# MAX30105_Breakout.net
KiCad netlist of a schematic drawn in EAGLE
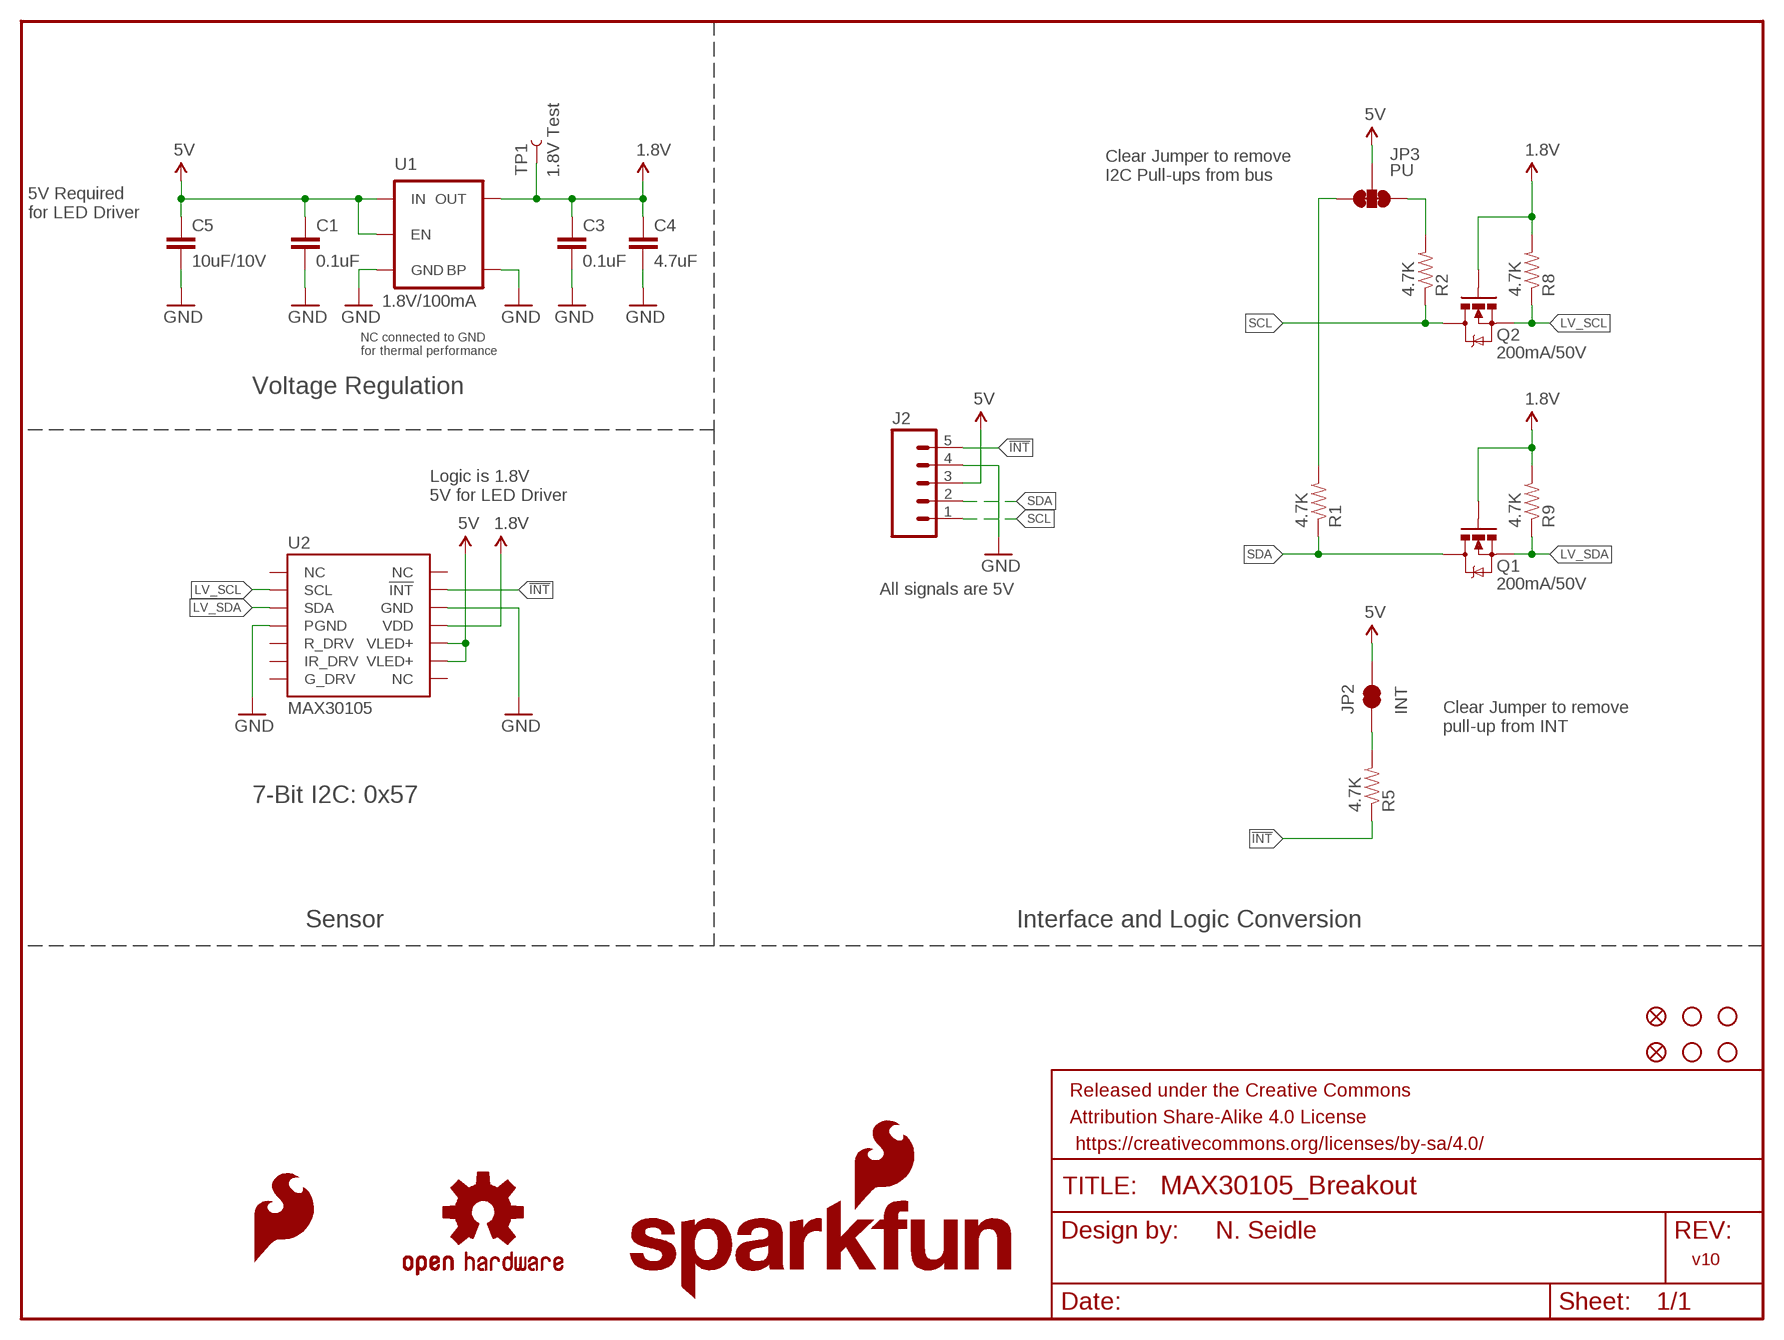
[diagram p0: schematic, sheet 1]

(export (version "E")
  (design (tool "Eeschema 10.0.6"))
  (components
    (comp (ref "C1")
      (value "0.1uF")
      (footprint "eagle-import:0603-CAP")
      (libsource (lib "eagle-import") (part "0.1UF-25V(+80/-20%)(0603)"))
    )
    (comp (ref "C3")
      (value "0.1uF")
      (footprint "eagle-import:0603-CAP")
      (libsource (lib "eagle-import") (part "0.1UF-25V(+80/-20%)(0603)"))
    )
    (comp (ref "C4")
      (value "4.7uF")
      (footprint "eagle-import:0603-CAP")
      (libsource (lib "eagle-import") (part "4.7UF-6.3V-10%(0603)0603"))
    )
    (comp (ref "C5")
      (value "10uF/10V")
      (footprint "eagle-import:0805-CAP")
      (libsource (lib "eagle-import") (part "10UF10V10%(0805)"))
    )
    (comp (ref "FID1")
      (value "FIDUCIAL1X2")
      (footprint "eagle-import:FIDUCIAL-1X2")
      (libsource (lib "eagle-import") (part "FIDUCIAL1X2"))
    )
    (comp (ref "FID2")
      (value "FIDUCIAL1X2")
      (footprint "eagle-import:FIDUCIAL-1X2")
      (libsource (lib "eagle-import") (part "FIDUCIAL1X2"))
    )
    (comp (ref "FRAME1")
      (value "FRAME-LETTER")
      (footprint "eagle-import:CREATIVE_COMMONS")
      (libsource (lib "eagle-import") (part "FRAME-LETTER"))
    )
    (comp (ref "J2")
      (value "M05PTH")
      (footprint "eagle-import:1X05")
      (libsource (lib "eagle-import") (part "M05PTH"))
    )
    (comp (ref "JP2")
      (value "INT")
      (footprint "eagle-import:PAD-JUMPER-2-NC_BY_TRACE_YES_SILK")
      (libsource (lib "eagle-import") (part "JUMPER-PAD-2-NC_BY_TRACE"))
    )
    (comp (ref "JP3")
      (value "PU")
      (footprint "eagle-import:PAD-JUMPER-3-3OF3_NC_BY_TRACE_YES_SILK_FULL_BOX")
      (libsource (lib "eagle-import") (part "JUMPER-PAD-3-NC_BY_TRACE"))
    )
    (comp (ref "LOGO1")
      (value "SFE_LOGO_NAME_FLAME.1_INCH")
      (footprint "eagle-import:SFE_LOGO_NAME_FLAME_.1")
      (libsource (lib "eagle-import") (part "SFE_LOGO_NAME_FLAME.1_INCH"))
    )
    (comp (ref "LOGO2")
      (value "OSHW-LOGOS")
      (footprint "eagle-import:OSHW-LOGO-S")
      (libsource (lib "eagle-import") (part "OSHW-LOGOS"))
    )
    (comp (ref "LOGO4")
      (value "SFE_LOGO_FLAME.1EXP")
      (footprint "eagle-import:SFE_LOGO_FLAME_COPPER_EXPOSED_.1")
      (libsource (lib "eagle-import") (part "SFE_LOGO_FLAME.1EXP"))
    )
    (comp (ref "Q1")
      (value "200mA/50V")
      (footprint "eagle-import:SOT23-3")
      (libsource (lib "eagle-import") (part "MOSFET-NCHANNELBSS138"))
    )
    (comp (ref "Q2")
      (value "200mA/50V")
      (footprint "eagle-import:SOT23-3")
      (libsource (lib "eagle-import") (part "MOSFET-NCHANNELBSS138"))
    )
    (comp (ref "R1")
      (value "4.7K")
      (footprint "eagle-import:0603-RES")
      (libsource (lib "eagle-import") (part "4.7KOHM-1/10W-1%(0603)"))
    )
    (comp (ref "R2")
      (value "4.7K")
      (footprint "eagle-import:0603-RES")
      (libsource (lib "eagle-import") (part "4.7KOHM-1/10W-1%(0603)"))
    )
    (comp (ref "R5")
      (value "4.7K")
      (footprint "eagle-import:0603-RES")
      (libsource (lib "eagle-import") (part "4.7KOHM-1/10W-1%(0603)"))
    )
    (comp (ref "R8")
      (value "4.7K")
      (footprint "eagle-import:0603-RES")
      (libsource (lib "eagle-import") (part "4.7KOHM-1/10W-1%(0603)"))
    )
    (comp (ref "R9")
      (value "4.7K")
      (footprint "eagle-import:0603-RES")
      (libsource (lib "eagle-import") (part "4.7KOHM-1/10W-1%(0603)"))
    )
    (comp (ref "STANDOFF1")
      (value "STAND-OFF")
      (footprint "eagle-import:STAND-OFF")
      (libsource (lib "eagle-import") (part "STAND-OFF"))
    )
    (comp (ref "STANDOFF2")
      (value "STAND-OFF")
      (footprint "eagle-import:STAND-OFF")
      (libsource (lib "eagle-import") (part "STAND-OFF"))
    )
    (comp (ref "STANDOFF3")
      (value "STAND-OFF")
      (footprint "eagle-import:STAND-OFF")
      (libsource (lib "eagle-import") (part "STAND-OFF"))
    )
    (comp (ref "STANDOFF4")
      (value "STAND-OFF")
      (footprint "eagle-import:STAND-OFF")
      (libsource (lib "eagle-import") (part "STAND-OFF"))
    )
    (comp (ref "TP1")
      (value "1.8V Test")
      (footprint "eagle-import:PAD.03X.04")
      (libsource (lib "eagle-import") (part "TEST-POINT3X4"))
    )
    (comp (ref "U1")
      (value "1.8V/100mA")
      (footprint "eagle-import:SC70")
      (libsource (lib "eagle-import") (part "V_REG_SP62141.8V"))
    )
    (comp (ref "U2")
      (value "MAX30105")
      (footprint "eagle-import:OLGA-14")
      (libsource (lib "eagle-import") (part "MAX30105SMD"))
    )
  )
  (nets
    (net (code "1") (name "/~{INT}") (class "Default")
      (node (ref "J2") (pin "5") (pinfunction "5_5") (pintype "passive"))
      (node (ref "R5") (pin "1") (pinfunction "1_1") (pintype "passive"))
      (node (ref "U2") (pin "13") (pinfunction "~{INT}_13") (pintype "bidirectional"))
    )
    (net (code "2") (name "1.8V") (class "Default")
      (node (ref "C3") (pin "1") (pinfunction "1_1") (pintype "passive"))
      (node (ref "C4") (pin "1") (pinfunction "1_1") (pintype "passive"))
      (node (ref "Q1") (pin "1") (pinfunction "G_1") (pintype "passive"))
      (node (ref "Q2") (pin "1") (pinfunction "G_1") (pintype "passive"))
      (node (ref "R8") (pin "2") (pinfunction "2_2") (pintype "passive"))
      (node (ref "R9") (pin "2") (pinfunction "2_2") (pintype "passive"))
      (node (ref "TP1") (pin "P$1") (pinfunction "1_P$1") (pintype "bidirectional"))
      (node (ref "U1") (pin "5") (pinfunction "OUT_5") (pintype "passive"))
      (node (ref "U2") (pin "11") (pinfunction "VDD_11") (pintype "bidirectional"))
    )
    (net (code "3") (name "5V") (class "Default")
      (node (ref "C1") (pin "1") (pinfunction "1_1") (pintype "passive"))
      (node (ref "C5") (pin "1") (pinfunction "1_1") (pintype "passive"))
      (node (ref "J2") (pin "3") (pinfunction "3_3") (pintype "passive"))
      (node (ref "JP2") (pin "2") (pinfunction "2_2") (pintype "passive"))
      (node (ref "JP3") (pin "2") (pinfunction "2_2") (pintype "passive"))
      (node (ref "U1") (pin "1") (pinfunction "IN_1") (pintype "input"))
      (node (ref "U1") (pin "3") (pinfunction "EN_3") (pintype "input"))
      (node (ref "U2") (pin "10") (pinfunction "VLED+_10") (pintype "bidirectional"))
      (node (ref "U2") (pin "9") (pinfunction "VLED+_9") (pintype "bidirectional"))
    )
    (net (code "4") (name "GND") (class "Default")
      (node (ref "C1") (pin "2") (pinfunction "2_2") (pintype "passive"))
      (node (ref "C3") (pin "2") (pinfunction "2_2") (pintype "passive"))
      (node (ref "C4") (pin "2") (pinfunction "2_2") (pintype "passive"))
      (node (ref "C5") (pin "2") (pinfunction "2_2") (pintype "passive"))
      (node (ref "J2") (pin "4") (pinfunction "4_4") (pintype "passive"))
      (node (ref "U1") (pin "2") (pinfunction "GND_2") (pintype "input"))
      (node (ref "U1") (pin "4") (pinfunction "BP_4") (pintype "input"))
      (node (ref "U2") (pin "12") (pinfunction "GND_12") (pintype "bidirectional"))
      (node (ref "U2") (pin "4") (pinfunction "PGND_4") (pintype "bidirectional"))
    )
    (net (code "5") (name "LV_SCL") (class "Default")
      (node (ref "Q2") (pin "2") (pinfunction "S_2") (pintype "passive"))
      (node (ref "R8") (pin "1") (pinfunction "1_1") (pintype "passive"))
      (node (ref "U2") (pin "2") (pinfunction "SCL_2") (pintype "bidirectional"))
    )
    (net (code "6") (name "LV_SDA") (class "Default")
      (node (ref "Q1") (pin "2") (pinfunction "S_2") (pintype "passive"))
      (node (ref "R9") (pin "1") (pinfunction "1_1") (pintype "passive"))
      (node (ref "U2") (pin "3") (pinfunction "SDA_3") (pintype "bidirectional"))
    )
    (net (code "7") (name "Net-(JP2-Pad1)") (class "Default")
      (node (ref "JP2") (pin "1") (pinfunction "1_1") (pintype "passive"))
      (node (ref "R5") (pin "2") (pinfunction "2_2") (pintype "passive"))
    )
    (net (code "8") (name "Net-(JP3-Pad1)") (class "Default")
      (node (ref "JP3") (pin "1") (pinfunction "1_1") (pintype "passive"))
      (node (ref "R2") (pin "2") (pinfunction "2_2") (pintype "passive"))
    )
    (net (code "9") (name "Net-(JP3-Pad3)") (class "Default")
      (node (ref "JP3") (pin "3") (pinfunction "3_3") (pintype "passive"))
      (node (ref "R1") (pin "2") (pinfunction "2_2") (pintype "passive"))
    )
    (net (code "10") (name "SCL") (class "Default")
      (node (ref "J2") (pin "1") (pinfunction "1_1") (pintype "passive"))
      (node (ref "Q2") (pin "3") (pinfunction "D_3") (pintype "passive"))
      (node (ref "R2") (pin "1") (pinfunction "1_1") (pintype "passive"))
    )
    (net (code "11") (name "SDA") (class "Default")
      (node (ref "J2") (pin "2") (pinfunction "2_2") (pintype "passive"))
      (node (ref "Q1") (pin "3") (pinfunction "D_3") (pintype "passive"))
      (node (ref "R1") (pin "1") (pinfunction "1_1") (pintype "passive"))
    )
    (net (code "12") (name "unconnected-(U2-G_DRV-Pad7)") (class "Default")
      (node (ref "U2") (pin "7") (pinfunction "G_DRV_7") (pintype "bidirectional"))
    )
    (net (code "13") (name "unconnected-(U2-IR_DRV-Pad6)") (class "Default")
      (node (ref "U2") (pin "6") (pinfunction "IR_DRV_6") (pintype "bidirectional"))
    )
    (net (code "14") (name "unconnected-(U2-NC-Pad1)") (class "Default")
      (node (ref "U2") (pin "1") (pinfunction "NC_1") (pintype "bidirectional"))
    )
    (net (code "15") (name "unconnected-(U2-NC-Pad8)") (class "Default")
      (node (ref "U2") (pin "8") (pinfunction "NC_8") (pintype "bidirectional"))
    )
    (net (code "16") (name "unconnected-(U2-NC-Pad14)") (class "Default")
      (node (ref "U2") (pin "14") (pinfunction "NC_14") (pintype "bidirectional"))
    )
    (net (code "17") (name "unconnected-(U2-R_DRV-Pad5)") (class "Default")
      (node (ref "U2") (pin "5") (pinfunction "R_DRV_5") (pintype "bidirectional"))
    )
  )
)
